# infrared.net
KiCad netlist of a schematic drawn in EAGLE
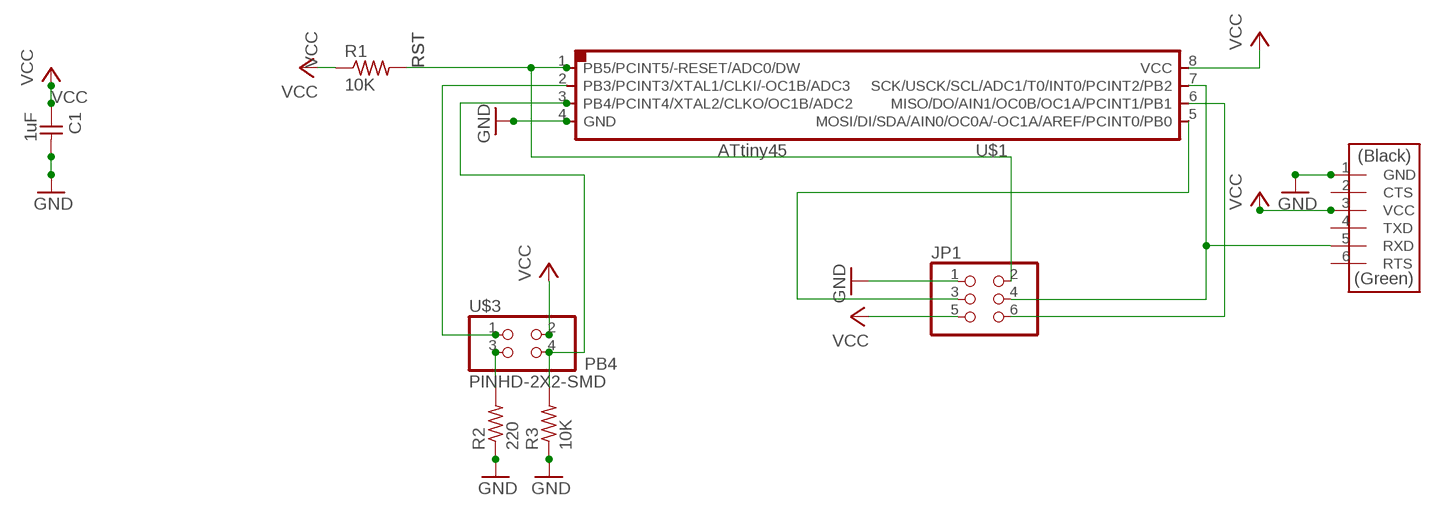
[diagram p0: schematic, sheet 1]

(export (version "E")
  (design (tool "Eeschema 10.0.6"))
  (components
    (comp (ref "C1")
      (value "1uF")
      (footprint "eagle-import:C1206FAB")
      (libsource (lib "eagle-import") (part "CAP-UNPOLARIZEDFAB"))
    )
    (comp (ref "JP1")
      (value "PINHD-2X3-SMD")
      (footprint "eagle-import:2X03SMD")
      (libsource (lib "eagle-import") (part "PINHD-2X3-SMD"))
    )
    (comp (ref "R1")
      (value "10K")
      (footprint "eagle-import:R1206FAB")
      (libsource (lib "eagle-import") (part "RES-US1206FAB"))
    )
    (comp (ref "R2")
      (value "220")
      (footprint "eagle-import:R1206FAB")
      (libsource (lib "eagle-import") (part "RES-US1206FAB"))
    )
    (comp (ref "R3")
      (value "10K")
      (footprint "eagle-import:R1206FAB")
      (libsource (lib "eagle-import") (part "RES-US1206FAB"))
    )
    (comp (ref "U$1")
      (value "ATTINY45SI")
      (footprint "eagle-import:SOIC8")
      (libsource (lib "eagle-import") (part "ATTINY45SI"))
    )
    (comp (ref "U$2")
      (value "FTDI-SMD-HEADER")
      (footprint "eagle-import:1X06SMD")
      (libsource (lib "eagle-import") (part "FTDI-SMD-HEADER"))
    )
    (comp (ref "U$3")
      (value "PINHD-2X2-SMD")
      (footprint "eagle-import:2X02SMD")
      (libsource (lib "eagle-import") (part "PINHD-2X2-SMD"))
    )
  )
  (nets
    (net (code "1") (name "/PB4") (class "Default")
      (node (ref "R3") (pin "2") (pinfunction "2_2") (pintype "passive"))
      (node (ref "U$1") (pin "3") (pinfunction "PB4/PCINT4/XTAL2/CLKO/OC1B/ADC2_3") (pintype "bidirectional"))
      (node (ref "U$3") (pin "4") (pinfunction "4_4") (pintype "passive"))
    )
    (net (code "2") (name "/RST") (class "Default")
      (node (ref "JP1") (pin "2") (pinfunction "2_2") (pintype "passive"))
      (node (ref "R1") (pin "2") (pinfunction "2_2") (pintype "passive"))
      (node (ref "U$1") (pin "1") (pinfunction "PB5/PCINT5/-RESET/ADC0/DW_1") (pintype "bidirectional"))
    )
    (net (code "3") (name "GND") (class "Default")
      (node (ref "C1") (pin "2") (pinfunction "2_2") (pintype "passive"))
      (node (ref "JP1") (pin "1") (pinfunction "1_1") (pintype "passive"))
      (node (ref "R2") (pin "1") (pinfunction "1_1") (pintype "passive"))
      (node (ref "R3") (pin "1") (pinfunction "1_1") (pintype "passive"))
      (node (ref "U$1") (pin "4") (pinfunction "GND_4") (pintype "bidirectional"))
      (node (ref "U$2") (pin "1") (pinfunction "GND_1") (pintype "bidirectional"))
    )
    (net (code "4") (name "Net-(R2-Pad2)") (class "Default")
      (node (ref "R2") (pin "2") (pinfunction "2_2") (pintype "passive"))
      (node (ref "U$3") (pin "3") (pinfunction "3_3") (pintype "passive"))
    )
    (net (code "5") (name "Net-(U$1-MISO{slash}DO{slash}AIN1{slash}OC0B{slash}OC1A{slash}PCINT1{slash}PB1)") (class "Default")
      (node (ref "JP1") (pin "6") (pinfunction "6_6") (pintype "passive"))
      (node (ref "U$1") (pin "6") (pinfunction "MISO/DO/AIN1/OC0B/OC1A/PCINT1/PB1_6") (pintype "bidirectional"))
    )
    (net (code "6") (name "Net-(U$1-MOSI{slash}DI{slash}SDA{slash}AIN0{slash}OC0A{slash}-OC1A{slash}AREF{slash}PCINT0{slash}PB0)") (class "Default")
      (node (ref "JP1") (pin "3") (pinfunction "3_3") (pintype "passive"))
      (node (ref "U$1") (pin "5") (pinfunction "MOSI/DI/SDA/AIN0/OC0A/-OC1A/AREF/PCINT0/PB0_5") (pintype "bidirectional"))
    )
    (net (code "7") (name "Net-(U$1-PB3{slash}PCINT3{slash}XTAL1{slash}CLKI{slash}-OC1B{slash}ADC3)") (class "Default")
      (node (ref "U$1") (pin "2") (pinfunction "PB3/PCINT3/XTAL1/CLKI/-OC1B/ADC3_2") (pintype "bidirectional"))
      (node (ref "U$3") (pin "1") (pinfunction "1_1") (pintype "passive"))
    )
    (net (code "8") (name "Net-(U$1-SCK{slash}USCK{slash}SCL{slash}ADC1{slash}T0{slash}INT0{slash}PCINT2{slash}PB2)") (class "Default")
      (node (ref "JP1") (pin "4") (pinfunction "4_4") (pintype "passive"))
      (node (ref "U$1") (pin "7") (pinfunction "SCK/USCK/SCL/ADC1/T0/INT0/PCINT2/PB2_7") (pintype "bidirectional"))
      (node (ref "U$2") (pin "5") (pinfunction "RXD_5") (pintype "bidirectional"))
    )
    (net (code "9") (name "VCC") (class "Default")
      (node (ref "C1") (pin "1") (pinfunction "1_1") (pintype "passive"))
      (node (ref "JP1") (pin "5") (pinfunction "5_5") (pintype "passive"))
      (node (ref "R1") (pin "1") (pinfunction "1_1") (pintype "passive"))
      (node (ref "U$1") (pin "8") (pinfunction "VCC_8") (pintype "bidirectional"))
      (node (ref "U$2") (pin "3") (pinfunction "VCC_3") (pintype "bidirectional"))
      (node (ref "U$3") (pin "2") (pinfunction "2_2") (pintype "passive"))
    )
    (net (code "10") (name "unconnected-(U$2-CTS-Pad2)") (class "Default")
      (node (ref "U$2") (pin "2") (pinfunction "CTS_2") (pintype "bidirectional"))
    )
    (net (code "11") (name "unconnected-(U$2-RTS-Pad6)") (class "Default")
      (node (ref "U$2") (pin "6") (pinfunction "RTS_6") (pintype "bidirectional"))
    )
    (net (code "12") (name "unconnected-(U$2-TXD-Pad4)") (class "Default")
      (node (ref "U$2") (pin "4") (pinfunction "TXD_4") (pintype "bidirectional"))
    )
  )
)
